# Sheet1.net
KiCad netlist of a schematic drawn in Altium Designer
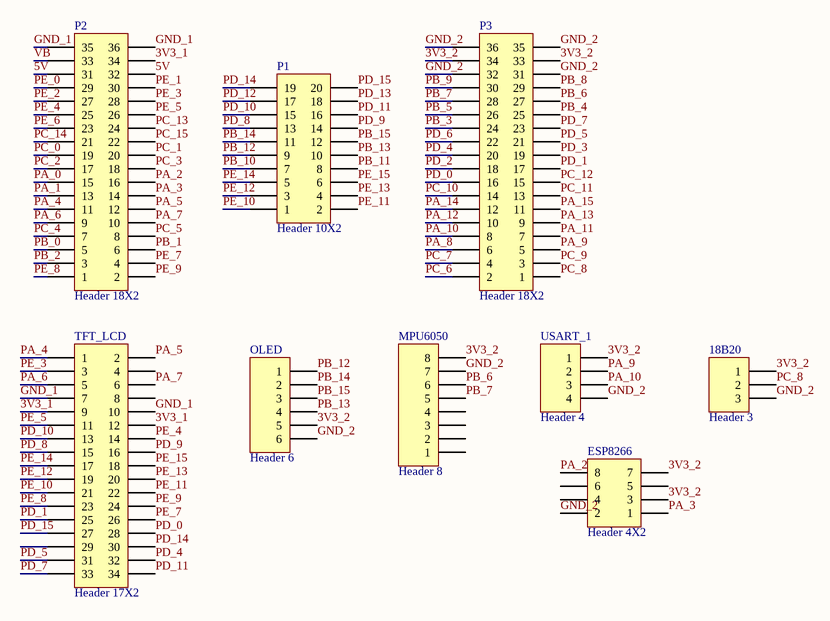
[diagram p0: Sheet1.SchDoc]

(export (version "E")
  (design (tool "Eeschema 10.0.6"))
  (components
    (comp (ref "18B20")
      (value "Header 3")
      (footprint "HDR1X3")
      (description "Header, 3-Pin")
      (fields (field (name "PUBLISHER") "Altium Limited"))
      (libsource (lib "Miscellaneous Connectors") (part "Header 3"))
    )
    (comp (ref "ESP8266")
      (value "Header 4X2")
      (footprint "HDR2X4")
      (description "Header, 4-Pin, Dual row")
      (fields (field (name "PUBLISHER") "Altium Limited"))
      (libsource (lib "Miscellaneous Connectors") (part "Header 4X2"))
    )
    (comp (ref "MPU6050")
      (value "Header 8")
      (footprint "HDR1X8")
      (description "Header, 8-Pin")
      (fields (field (name "PUBLISHER") "Altium Limited"))
      (libsource (lib "Miscellaneous Connectors") (part "Header 8"))
    )
    (comp (ref "OLED")
      (value "Header 6")
      (footprint "HDR1X6")
      (description "Header, 6-Pin")
      (fields (field (name "PUBLISHER") "Altium Limited"))
      (libsource (lib "Miscellaneous Connectors") (part "Header 6"))
    )
    (comp (ref "P1")
      (value "Header 10X2")
      (footprint "HDR2X10")
      (description "Header, 10-Pin, Dual row")
      (fields (field (name "PUBLISHER") "Altium Limited"))
      (libsource (lib "STM32F407VET6mini最小系统-原理图库") (part "Header 10X2"))
    )
    (comp (ref "P2")
      (value "Header 18X2")
      (footprint "HDR2X18")
      (description "Header, 18-Pin, Dual row")
      (fields (field (name "PUBLISHER") "Altium Limited"))
      (libsource (lib "STM32F407VET6mini最小系统-原理图库") (part "Header 18X2"))
    )
    (comp (ref "P3")
      (value "Header 18X2")
      (footprint "HDR2X18")
      (description "Header, 18-Pin, Dual row")
      (fields (field (name "PUBLISHER") "Altium Limited"))
      (libsource (lib "") (part "Header 18X2_1"))
    )
    (comp (ref "TFT_LCD")
      (value "Header 17X2")
      (footprint "HDR2X17")
      (description "Header, 17-Pin, Dual row")
      (fields (field (name "PUBLISHER") "Altium Limited"))
      (libsource (lib "Miscellaneous Connectors") (part "Header 17X2"))
    )
    (comp (ref "USART_1")
      (value "Header 4")
      (footprint "HDR1X4")
      (description "Header, 4-Pin")
      (fields (field (name "PUBLISHER") "Altium Limited"))
      (libsource (lib "Miscellaneous Connectors") (part "Header 4"))
    )
  )
  (nets
    (net (code "1") (name "/3V3_1") (class "Default")
      (node (ref "P2") (pin "34") (pinfunction "34_34") (pintype "passive"))
      (node (ref "TFT_LCD") (pin "12") (pinfunction "12_12") (pintype "passive"))
      (node (ref "TFT_LCD") (pin "9") (pinfunction "9_9") (pintype "passive"))
    )
    (net (code "2") (name "/3V3_2") (class "Default")
      (node (ref "18B20") (pin "1") (pinfunction "1_1") (pintype "passive"))
      (node (ref "ESP8266") (pin "3") (pinfunction "3_3") (pintype "passive"))
      (node (ref "ESP8266") (pin "7") (pinfunction "7_7") (pintype "passive"))
      (node (ref "MPU6050") (pin "8") (pinfunction "8_8") (pintype "passive"))
      (node (ref "OLED") (pin "5") (pinfunction "5_5") (pintype "passive"))
      (node (ref "P3") (pin "33") (pinfunction "33_33") (pintype "passive"))
      (node (ref "P3") (pin "34") (pinfunction "34_34") (pintype "passive"))
      (node (ref "USART_1") (pin "1") (pinfunction "1_1") (pintype "passive"))
    )
    (net (code "3") (name "/5V") (class "Default")
      (node (ref "P2") (pin "31") (pinfunction "31_31") (pintype "passive"))
      (node (ref "P2") (pin "32") (pinfunction "32_32") (pintype "passive"))
    )
    (net (code "4") (name "/GND_1") (class "Default")
      (node (ref "P2") (pin "35") (pinfunction "35_35") (pintype "passive"))
      (node (ref "P2") (pin "36") (pinfunction "36_36") (pintype "passive"))
      (node (ref "TFT_LCD") (pin "10") (pinfunction "10_10") (pintype "passive"))
      (node (ref "TFT_LCD") (pin "7") (pinfunction "7_7") (pintype "passive"))
    )
    (net (code "5") (name "/GND_2") (class "Default")
      (node (ref "18B20") (pin "3") (pinfunction "3_3") (pintype "passive"))
      (node (ref "ESP8266") (pin "2") (pinfunction "2_2") (pintype "passive"))
      (node (ref "MPU6050") (pin "7") (pinfunction "7_7") (pintype "passive"))
      (node (ref "OLED") (pin "6") (pinfunction "6_6") (pintype "passive"))
      (node (ref "P3") (pin "31") (pinfunction "31_31") (pintype "passive"))
      (node (ref "P3") (pin "32") (pinfunction "32_32") (pintype "passive"))
      (node (ref "P3") (pin "35") (pinfunction "35_35") (pintype "passive"))
      (node (ref "P3") (pin "36") (pinfunction "36_36") (pintype "passive"))
      (node (ref "USART_1") (pin "4") (pinfunction "4_4") (pintype "passive"))
    )
    (net (code "6") (name "/PA_0") (class "Default")
      (node (ref "P2") (pin "15") (pinfunction "15_15") (pintype "passive"))
    )
    (net (code "7") (name "/PA_1") (class "Default")
      (node (ref "P2") (pin "13") (pinfunction "13_13") (pintype "passive"))
    )
    (net (code "8") (name "/PA_2") (class "Default")
      (node (ref "ESP8266") (pin "8") (pinfunction "8_8") (pintype "passive"))
      (node (ref "P2") (pin "16") (pinfunction "16_16") (pintype "passive"))
    )
    (net (code "9") (name "/PA_3") (class "Default")
      (node (ref "ESP8266") (pin "1") (pinfunction "1_1") (pintype "passive"))
      (node (ref "P2") (pin "14") (pinfunction "14_14") (pintype "passive"))
    )
    (net (code "10") (name "/PA_4") (class "Default")
      (node (ref "P2") (pin "11") (pinfunction "11_11") (pintype "passive"))
      (node (ref "TFT_LCD") (pin "1") (pinfunction "1_1") (pintype "passive"))
    )
    (net (code "11") (name "/PA_5") (class "Default")
      (node (ref "P2") (pin "12") (pinfunction "12_12") (pintype "passive"))
      (node (ref "TFT_LCD") (pin "2") (pinfunction "2_2") (pintype "passive"))
    )
    (net (code "12") (name "/PA_6") (class "Default")
      (node (ref "P2") (pin "9") (pinfunction "9_9") (pintype "passive"))
      (node (ref "TFT_LCD") (pin "5") (pinfunction "5_5") (pintype "passive"))
    )
    (net (code "13") (name "/PA_7") (class "Default")
      (node (ref "P2") (pin "10") (pinfunction "10_10") (pintype "passive"))
      (node (ref "TFT_LCD") (pin "6") (pinfunction "6_6") (pintype "passive"))
    )
    (net (code "14") (name "/PA_8") (class "Default")
      (node (ref "P3") (pin "6") (pinfunction "6_6") (pintype "passive"))
    )
    (net (code "15") (name "/PA_9") (class "Default")
      (node (ref "P3") (pin "5") (pinfunction "5_5") (pintype "passive"))
      (node (ref "USART_1") (pin "2") (pinfunction "2_2") (pintype "passive"))
    )
    (net (code "16") (name "/PA_10") (class "Default")
      (node (ref "P3") (pin "8") (pinfunction "8_8") (pintype "passive"))
      (node (ref "USART_1") (pin "3") (pinfunction "3_3") (pintype "passive"))
    )
    (net (code "17") (name "/PA_11") (class "Default")
      (node (ref "P3") (pin "7") (pinfunction "7_7") (pintype "passive"))
    )
    (net (code "18") (name "/PA_12") (class "Default")
      (node (ref "P3") (pin "10") (pinfunction "10_10") (pintype "passive"))
    )
    (net (code "19") (name "/PA_13") (class "Default")
      (node (ref "P3") (pin "9") (pinfunction "9_9") (pintype "passive"))
    )
    (net (code "20") (name "/PA_14") (class "Default")
      (node (ref "P3") (pin "12") (pinfunction "12_12") (pintype "passive"))
    )
    (net (code "21") (name "/PA_15") (class "Default")
      (node (ref "P3") (pin "11") (pinfunction "11_11") (pintype "passive"))
    )
    (net (code "22") (name "/PB_0") (class "Default")
      (node (ref "P2") (pin "5") (pinfunction "5_5") (pintype "passive"))
    )
    (net (code "23") (name "/PB_1") (class "Default")
      (node (ref "P2") (pin "6") (pinfunction "6_6") (pintype "passive"))
    )
    (net (code "24") (name "/PB_2") (class "Default")
      (node (ref "P2") (pin "3") (pinfunction "3_3") (pintype "passive"))
    )
    (net (code "25") (name "/PB_3") (class "Default")
      (node (ref "P3") (pin "24") (pinfunction "24_24") (pintype "passive"))
    )
    (net (code "26") (name "/PB_4") (class "Default")
      (node (ref "P3") (pin "25") (pinfunction "25_25") (pintype "passive"))
    )
    (net (code "27") (name "/PB_5") (class "Default")
      (node (ref "P3") (pin "26") (pinfunction "26_26") (pintype "passive"))
    )
    (net (code "28") (name "/PB_6") (class "Default")
      (node (ref "MPU6050") (pin "6") (pinfunction "6_6") (pintype "passive"))
      (node (ref "P3") (pin "27") (pinfunction "27_27") (pintype "passive"))
    )
    (net (code "29") (name "/PB_7") (class "Default")
      (node (ref "MPU6050") (pin "5") (pinfunction "5_5") (pintype "passive"))
      (node (ref "P3") (pin "28") (pinfunction "28_28") (pintype "passive"))
    )
    (net (code "30") (name "/PB_8") (class "Default")
      (node (ref "P3") (pin "29") (pinfunction "29_29") (pintype "passive"))
    )
    (net (code "31") (name "/PB_9") (class "Default")
      (node (ref "P3") (pin "30") (pinfunction "30_30") (pintype "passive"))
    )
    (net (code "32") (name "/PB_10") (class "Default")
      (node (ref "P1") (pin "7") (pinfunction "7_7") (pintype "passive"))
    )
    (net (code "33") (name "/PB_11") (class "Default")
      (node (ref "P1") (pin "8") (pinfunction "8_8") (pintype "passive"))
    )
    (net (code "34") (name "/PB_12") (class "Default")
      (node (ref "OLED") (pin "1") (pinfunction "1_1") (pintype "passive"))
      (node (ref "P1") (pin "9") (pinfunction "9_9") (pintype "passive"))
    )
    (net (code "35") (name "/PB_13") (class "Default")
      (node (ref "OLED") (pin "4") (pinfunction "4_4") (pintype "passive"))
      (node (ref "P1") (pin "10") (pinfunction "10_10") (pintype "passive"))
    )
    (net (code "36") (name "/PB_14") (class "Default")
      (node (ref "OLED") (pin "2") (pinfunction "2_2") (pintype "passive"))
      (node (ref "P1") (pin "11") (pinfunction "11_11") (pintype "passive"))
    )
    (net (code "37") (name "/PB_15") (class "Default")
      (node (ref "OLED") (pin "3") (pinfunction "3_3") (pintype "passive"))
      (node (ref "P1") (pin "12") (pinfunction "12_12") (pintype "passive"))
    )
    (net (code "38") (name "/PC_0") (class "Default")
      (node (ref "P2") (pin "19") (pinfunction "19_19") (pintype "passive"))
    )
    (net (code "39") (name "/PC_1") (class "Default")
      (node (ref "P2") (pin "20") (pinfunction "20_20") (pintype "passive"))
    )
    (net (code "40") (name "/PC_2") (class "Default")
      (node (ref "P2") (pin "17") (pinfunction "17_17") (pintype "passive"))
    )
    (net (code "41") (name "/PC_3") (class "Default")
      (node (ref "P2") (pin "18") (pinfunction "18_18") (pintype "passive"))
    )
    (net (code "42") (name "/PC_4") (class "Default")
      (node (ref "P2") (pin "7") (pinfunction "7_7") (pintype "passive"))
    )
    (net (code "43") (name "/PC_5") (class "Default")
      (node (ref "P2") (pin "8") (pinfunction "8_8") (pintype "passive"))
    )
    (net (code "44") (name "/PC_6") (class "Default")
      (node (ref "P3") (pin "2") (pinfunction "2_2") (pintype "passive"))
    )
    (net (code "45") (name "/PC_7") (class "Default")
      (node (ref "P3") (pin "4") (pinfunction "4_4") (pintype "passive"))
    )
    (net (code "46") (name "/PC_8") (class "Default")
      (node (ref "18B20") (pin "2") (pinfunction "2_2") (pintype "passive"))
      (node (ref "P3") (pin "1") (pinfunction "1_1") (pintype "passive"))
    )
    (net (code "47") (name "/PC_9") (class "Default")
      (node (ref "P3") (pin "3") (pinfunction "3_3") (pintype "passive"))
    )
    (net (code "48") (name "/PC_10") (class "Default")
      (node (ref "P3") (pin "14") (pinfunction "14_14") (pintype "passive"))
    )
    (net (code "49") (name "/PC_11") (class "Default")
      (node (ref "P3") (pin "13") (pinfunction "13_13") (pintype "passive"))
    )
    (net (code "50") (name "/PC_12") (class "Default")
      (node (ref "P3") (pin "15") (pinfunction "15_15") (pintype "passive"))
    )
    (net (code "51") (name "/PC_13") (class "Default")
      (node (ref "P2") (pin "24") (pinfunction "24_24") (pintype "passive"))
    )
    (net (code "52") (name "/PC_14") (class "Default")
      (node (ref "P2") (pin "21") (pinfunction "21_21") (pintype "passive"))
    )
    (net (code "53") (name "/PC_15") (class "Default")
      (node (ref "P2") (pin "22") (pinfunction "22_22") (pintype "passive"))
    )
    (net (code "54") (name "/PD_0") (class "Default")
      (node (ref "P3") (pin "16") (pinfunction "16_16") (pintype "passive"))
      (node (ref "TFT_LCD") (pin "28") (pinfunction "28_28") (pintype "passive"))
    )
    (net (code "55") (name "/PD_1") (class "Default")
      (node (ref "P3") (pin "17") (pinfunction "17_17") (pintype "passive"))
      (node (ref "TFT_LCD") (pin "25") (pinfunction "25_25") (pintype "passive"))
    )
    (net (code "56") (name "/PD_2") (class "Default")
      (node (ref "P3") (pin "18") (pinfunction "18_18") (pintype "passive"))
    )
    (net (code "57") (name "/PD_3") (class "Default")
      (node (ref "P3") (pin "19") (pinfunction "19_19") (pintype "passive"))
    )
    (net (code "58") (name "/PD_4") (class "Default")
      (node (ref "P3") (pin "20") (pinfunction "20_20") (pintype "passive"))
      (node (ref "TFT_LCD") (pin "32") (pinfunction "32_32") (pintype "passive"))
    )
    (net (code "59") (name "/PD_5") (class "Default")
      (node (ref "P3") (pin "21") (pinfunction "21_21") (pintype "passive"))
      (node (ref "TFT_LCD") (pin "31") (pinfunction "31_31") (pintype "passive"))
    )
    (net (code "60") (name "/PD_6") (class "Default")
      (node (ref "P3") (pin "22") (pinfunction "22_22") (pintype "passive"))
    )
    (net (code "61") (name "/PD_7") (class "Default")
      (node (ref "P3") (pin "23") (pinfunction "23_23") (pintype "passive"))
      (node (ref "TFT_LCD") (pin "33") (pinfunction "33_33") (pintype "passive"))
    )
    (net (code "62") (name "/PD_8") (class "Default")
      (node (ref "P1") (pin "13") (pinfunction "13_13") (pintype "passive"))
      (node (ref "TFT_LCD") (pin "15") (pinfunction "15_15") (pintype "passive"))
    )
    (net (code "63") (name "/PD_9") (class "Default")
      (node (ref "P1") (pin "14") (pinfunction "14_14") (pintype "passive"))
      (node (ref "TFT_LCD") (pin "16") (pinfunction "16_16") (pintype "passive"))
    )
    (net (code "64") (name "/PD_10") (class "Default")
      (node (ref "P1") (pin "15") (pinfunction "15_15") (pintype "passive"))
      (node (ref "TFT_LCD") (pin "13") (pinfunction "13_13") (pintype "passive"))
    )
    (net (code "65") (name "/PD_11") (class "Default")
      (node (ref "P1") (pin "16") (pinfunction "16_16") (pintype "passive"))
      (node (ref "TFT_LCD") (pin "34") (pinfunction "34_34") (pintype "passive"))
    )
    (net (code "66") (name "/PD_12") (class "Default")
      (node (ref "P1") (pin "17") (pinfunction "17_17") (pintype "passive"))
    )
    (net (code "67") (name "/PD_13") (class "Default")
      (node (ref "P1") (pin "18") (pinfunction "18_18") (pintype "passive"))
    )
    (net (code "68") (name "/PD_14") (class "Default")
      (node (ref "P1") (pin "19") (pinfunction "19_19") (pintype "passive"))
      (node (ref "TFT_LCD") (pin "30") (pinfunction "30_30") (pintype "passive"))
    )
    (net (code "69") (name "/PD_15") (class "Default")
      (node (ref "P1") (pin "20") (pinfunction "20_20") (pintype "passive"))
      (node (ref "TFT_LCD") (pin "27") (pinfunction "27_27") (pintype "passive"))
    )
    (net (code "70") (name "/PE_0") (class "Default")
      (node (ref "P2") (pin "29") (pinfunction "29_29") (pintype "passive"))
    )
    (net (code "71") (name "/PE_1") (class "Default")
      (node (ref "P2") (pin "30") (pinfunction "30_30") (pintype "passive"))
    )
    (net (code "72") (name "/PE_2") (class "Default")
      (node (ref "P2") (pin "27") (pinfunction "27_27") (pintype "passive"))
    )
    (net (code "73") (name "/PE_3") (class "Default")
      (node (ref "P2") (pin "28") (pinfunction "28_28") (pintype "passive"))
      (node (ref "TFT_LCD") (pin "3") (pinfunction "3_3") (pintype "passive"))
    )
    (net (code "74") (name "/PE_4") (class "Default")
      (node (ref "P2") (pin "25") (pinfunction "25_25") (pintype "passive"))
      (node (ref "TFT_LCD") (pin "14") (pinfunction "14_14") (pintype "passive"))
    )
    (net (code "75") (name "/PE_5") (class "Default")
      (node (ref "P2") (pin "26") (pinfunction "26_26") (pintype "passive"))
      (node (ref "TFT_LCD") (pin "11") (pinfunction "11_11") (pintype "passive"))
    )
    (net (code "76") (name "/PE_6") (class "Default")
      (node (ref "P2") (pin "23") (pinfunction "23_23") (pintype "passive"))
    )
    (net (code "77") (name "/PE_7") (class "Default")
      (node (ref "P2") (pin "4") (pinfunction "4_4") (pintype "passive"))
      (node (ref "TFT_LCD") (pin "26") (pinfunction "26_26") (pintype "passive"))
    )
    (net (code "78") (name "/PE_8") (class "Default")
      (node (ref "P2") (pin "1") (pinfunction "1_1") (pintype "passive"))
      (node (ref "TFT_LCD") (pin "23") (pinfunction "23_23") (pintype "passive"))
    )
    (net (code "79") (name "/PE_9") (class "Default")
      (node (ref "P2") (pin "2") (pinfunction "2_2") (pintype "passive"))
      (node (ref "TFT_LCD") (pin "24") (pinfunction "24_24") (pintype "passive"))
    )
    (net (code "80") (name "/PE_10") (class "Default")
      (node (ref "P1") (pin "1") (pinfunction "1_1") (pintype "passive"))
      (node (ref "TFT_LCD") (pin "21") (pinfunction "21_21") (pintype "passive"))
    )
    (net (code "81") (name "/PE_11") (class "Default")
      (node (ref "P1") (pin "2") (pinfunction "2_2") (pintype "passive"))
      (node (ref "TFT_LCD") (pin "22") (pinfunction "22_22") (pintype "passive"))
    )
    (net (code "82") (name "/PE_12") (class "Default")
      (node (ref "P1") (pin "3") (pinfunction "3_3") (pintype "passive"))
      (node (ref "TFT_LCD") (pin "19") (pinfunction "19_19") (pintype "passive"))
    )
    (net (code "83") (name "/PE_13") (class "Default")
      (node (ref "P1") (pin "4") (pinfunction "4_4") (pintype "passive"))
      (node (ref "TFT_LCD") (pin "20") (pinfunction "20_20") (pintype "passive"))
    )
    (net (code "84") (name "/PE_14") (class "Default")
      (node (ref "P1") (pin "5") (pinfunction "5_5") (pintype "passive"))
      (node (ref "TFT_LCD") (pin "17") (pinfunction "17_17") (pintype "passive"))
    )
    (net (code "85") (name "/PE_15") (class "Default")
      (node (ref "P1") (pin "6") (pinfunction "6_6") (pintype "passive"))
      (node (ref "TFT_LCD") (pin "18") (pinfunction "18_18") (pintype "passive"))
    )
    (net (code "86") (name "/VB") (class "Default")
      (node (ref "P2") (pin "33") (pinfunction "33_33") (pintype "passive"))
    )
    (net (code "87") (name "unconnected-(ESP8266-Pad4)") (class "Default")
      (node (ref "ESP8266") (pin "4") (pinfunction "4_4") (pintype "passive"))
    )
    (net (code "88") (name "unconnected-(ESP8266-Pad5)") (class "Default")
      (node (ref "ESP8266") (pin "5") (pinfunction "5_5") (pintype "passive"))
    )
    (net (code "89") (name "unconnected-(ESP8266-Pad6)") (class "Default")
      (node (ref "ESP8266") (pin "6") (pinfunction "6_6") (pintype "passive"))
    )
    (net (code "90") (name "unconnected-(MPU6050-Pad1)") (class "Default")
      (node (ref "MPU6050") (pin "1") (pinfunction "1_1") (pintype "passive"))
    )
    (net (code "91") (name "unconnected-(MPU6050-Pad2)") (class "Default")
      (node (ref "MPU6050") (pin "2") (pinfunction "2_2") (pintype "passive"))
    )
    (net (code "92") (name "unconnected-(MPU6050-Pad3)") (class "Default")
      (node (ref "MPU6050") (pin "3") (pinfunction "3_3") (pintype "passive"))
    )
    (net (code "93") (name "unconnected-(MPU6050-Pad4)") (class "Default")
      (node (ref "MPU6050") (pin "4") (pinfunction "4_4") (pintype "passive"))
    )
    (net (code "94") (name "unconnected-(TFT_LCD-Pad4)") (class "Default")
      (node (ref "TFT_LCD") (pin "4") (pinfunction "4_4") (pintype "passive"))
    )
    (net (code "95") (name "unconnected-(TFT_LCD-Pad8)") (class "Default")
      (node (ref "TFT_LCD") (pin "8") (pinfunction "8_8") (pintype "passive"))
    )
    (net (code "96") (name "unconnected-(TFT_LCD-Pad29)") (class "Default")
      (node (ref "TFT_LCD") (pin "29") (pinfunction "29_29") (pintype "passive"))
    )
  )
)
